# design.net
KiCad netlist of a schematic drawn in Altium Designer
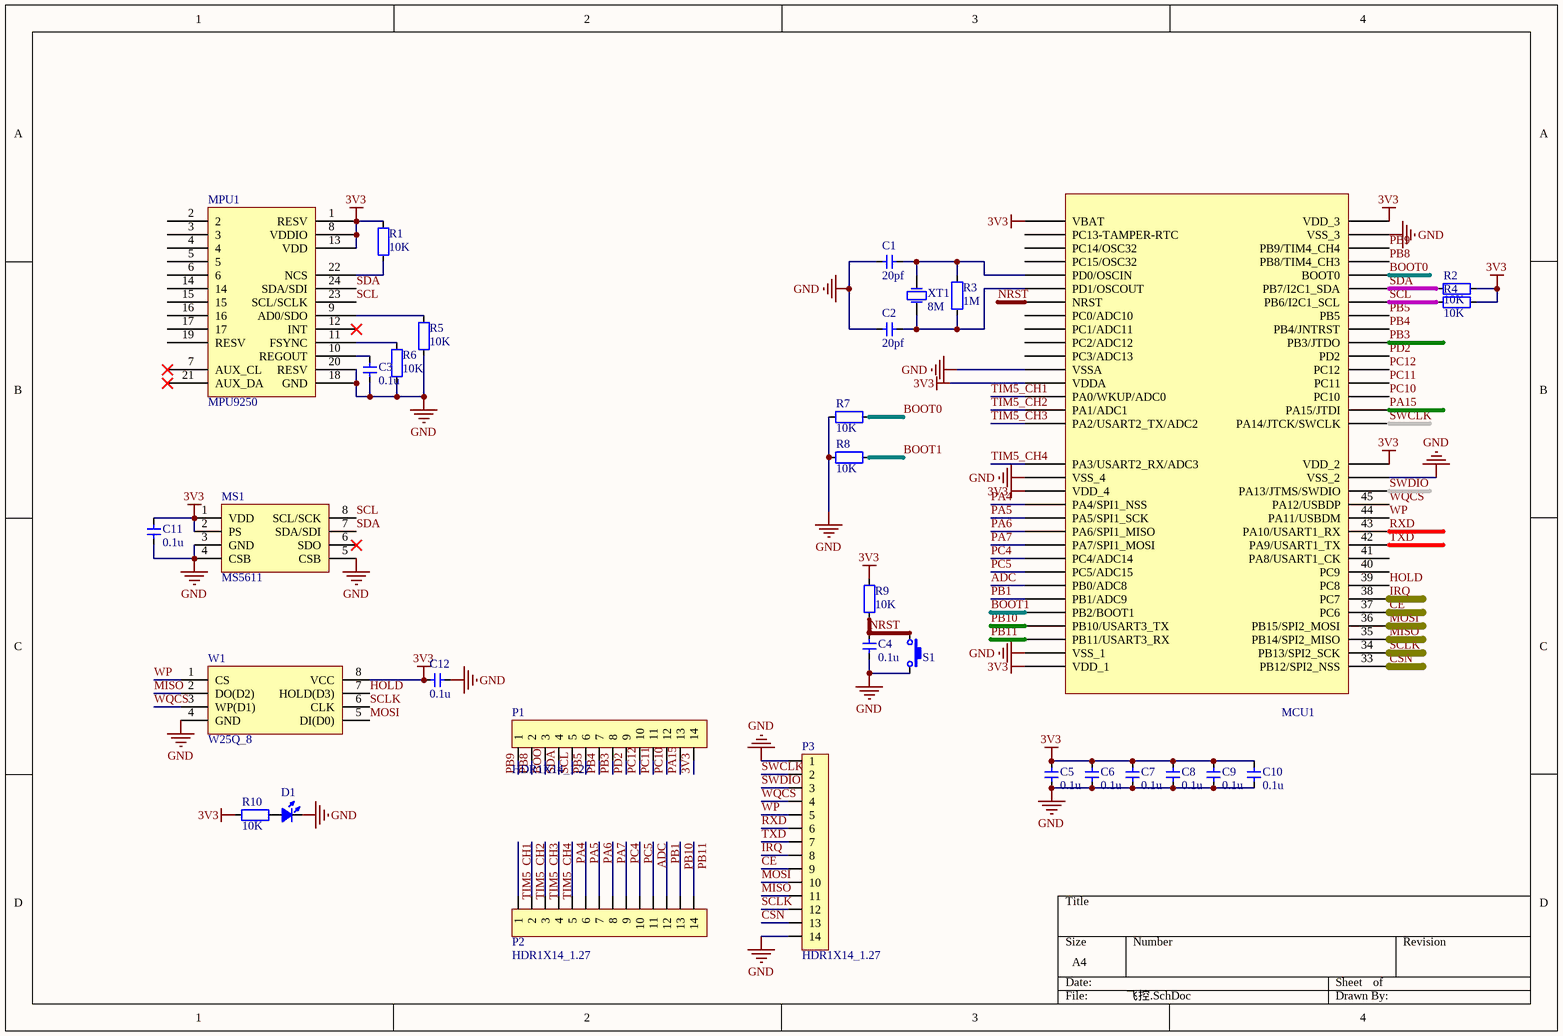
[diagram p0: 飞控.SchDoc]

(export (version "E")
  (design (tool "Eeschema 10.0.6"))
  (components
    (comp (ref "C1")
      (value "20pf")
      (footprint "PCB_PassiveCap:CAP_0603")
      (description "Capacitor")
      (fields (field (name "Comment") "Cap_0603"))
      (libsource (lib "SCH_Passive") (part "Cap_0603"))
    )
    (comp (ref "C2")
      (value "20pf")
      (footprint "PCB_PassiveCap:CAP_0603")
      (description "Capacitor")
      (fields (field (name "Comment") "Cap_0603"))
      (libsource (lib "SCH_Passive") (part "Cap_0603"))
    )
    (comp (ref "C3")
      (value "0.1u")
      (footprint "PCB_PassiveCap:CAP_0603")
      (description "Capacitor")
      (fields (field (name "Comment") "Cap_0603"))
      (libsource (lib "SCH_Passive") (part "Cap_0603"))
    )
    (comp (ref "C4")
      (value "0.1u")
      (footprint "PCB_PassiveCap:CAP_0603")
      (description "Capacitor")
      (fields (field (name "Comment") "Cap_0603"))
      (libsource (lib "SCH_Passive") (part "Cap_0603"))
    )
    (comp (ref "C5")
      (value "0.1u")
      (footprint "PCB_PassiveCap:CAP_0603")
      (description "Capacitor")
      (fields (field (name "Comment") "Cap_0603"))
      (libsource (lib "SCH_Passive") (part "Cap_0603"))
    )
    (comp (ref "C6")
      (value "0.1u")
      (footprint "PCB_PassiveCap:CAP_0603")
      (description "Capacitor")
      (fields (field (name "Comment") "Cap_0603"))
      (libsource (lib "SCH_Passive") (part "Cap_0603"))
    )
    (comp (ref "C7")
      (value "0.1u")
      (footprint "PCB_PassiveCap:CAP_0603")
      (description "Capacitor")
      (fields (field (name "Comment") "Cap_0603"))
      (libsource (lib "SCH_Passive") (part "Cap_0603"))
    )
    (comp (ref "C8")
      (value "0.1u")
      (footprint "PCB_PassiveCap:CAP_0603")
      (description "Capacitor")
      (fields (field (name "Comment") "Cap_0603"))
      (libsource (lib "SCH_Passive") (part "Cap_0603"))
    )
    (comp (ref "C9")
      (value "0.1u")
      (footprint "PCB_PassiveCap:CAP_0603")
      (description "Capacitor")
      (fields (field (name "Comment") "Cap_0603"))
      (libsource (lib "SCH_Passive") (part "Cap_0603"))
    )
    (comp (ref "C10")
      (value "0.1u")
      (footprint "PCB_PassiveCap:CAP_0603")
      (description "Capacitor")
      (fields (field (name "Comment") "Cap_0603"))
      (libsource (lib "SCH_Passive") (part "Cap_0603"))
    )
    (comp (ref "C11")
      (value "0.1u")
      (footprint "PCB_PassiveCap:CAP_0603")
      (description "Capacitor")
      (fields (field (name "Comment") "Cap_0603"))
      (libsource (lib "SCH_Passive") (part "Cap_0603"))
    )
    (comp (ref "C12")
      (value "0.1u")
      (footprint "PCB_PassiveCap:CAP_0603")
      (description "Capacitor")
      (fields (field (name "Comment") "Cap_0603"))
      (libsource (lib "SCH_Passive") (part "Cap_0603"))
    )
    (comp (ref "D1")
      (value "LED_0805")
      (footprint "PCB_ActiveLED:LED_0805_RED")
      (description "LED")
      (libsource (lib "SCH_Active") (part "LED_0805"))
    )
    (comp (ref "MCU1")
      (value "STM32F103RC")
      (footprint "LQFP_P0.5_64")
      (description "MCU")
      (libsource (lib "SCH_IntegratedCircuit") (part "STM32F103RC"))
    )
    (comp (ref "MPU1")
      (value "MPU9250")
      (footprint "QFN_P0.4_24")
      (libsource (lib "K60-mainboard-v3.1") (part "MPU9250"))
    )
    (comp (ref "MS1")
      (value "MS5611")
      (footprint "PCB_IntegratedCircuit:OTHER_MS5611_8")
      (description "Sensor")
      (libsource (lib "SCH_IntegratedCircuit") (part "MS5611"))
    )
    (comp (ref "P1")
      (value "HDR1X14_1.27")
      (footprint "HDR1X14_1.27")
      (libsource (lib "") (part "HDR1X14_1.27_2"))
    )
    (comp (ref "P2")
      (value "HDR1X14_1.27")
      (footprint "HDR1X14_1.27")
      (libsource (lib "") (part "HDR1X14_1.27_1"))
    )
    (comp (ref "P3")
      (value "HDR1X14_1.27")
      (footprint "HDR1X14_1.27")
      (libsource (lib "SCH_ConnectorHDR") (part "HDR1X14_1.27"))
    )
    (comp (ref "R1")
      (value "10K")
      (footprint "PCB_PassiveRes:RES_0603")
      (description "Resistor")
      (fields (field (name "Comment") "Res_0603"))
      (libsource (lib "SCH_Passive") (part "Res_0603"))
    )
    (comp (ref "R2")
      (value "10K")
      (footprint "PCB_PassiveRes:RES_0603")
      (description "Resistor")
      (fields (field (name "Comment") "Res_0603"))
      (libsource (lib "") (part "Res_0603_1"))
    )
    (comp (ref "R3")
      (value "1M")
      (footprint "PCB_PassiveRes:RES_0603")
      (description "Resistor")
      (fields (field (name "Comment") "Res_0603"))
      (libsource (lib "") (part "Res_0603_2"))
    )
    (comp (ref "R4")
      (value "10K")
      (footprint "PCB_PassiveRes:RES_0603")
      (description "Resistor")
      (fields (field (name "Comment") "Res_0603"))
      (libsource (lib "") (part "Res_0603_1"))
    )
    (comp (ref "R5")
      (value "10K")
      (footprint "PCB_PassiveRes:RES_0603")
      (description "Resistor")
      (fields (field (name "Comment") "Res_0603"))
      (libsource (lib "SCH_Passive") (part "Res_0603"))
    )
    (comp (ref "R6")
      (value "10K")
      (footprint "PCB_PassiveRes:RES_0603")
      (description "Resistor")
      (fields (field (name "Comment") "Res_0603"))
      (libsource (lib "SCH_Passive") (part "Res_0603"))
    )
    (comp (ref "R7")
      (value "10K")
      (footprint "PCB_PassiveRes:RES_0603")
      (description "Resistor")
      (fields (field (name "Comment") "Res_0603"))
      (libsource (lib "") (part "Res_0603_3"))
    )
    (comp (ref "R8")
      (value "10K")
      (footprint "PCB_PassiveRes:RES_0603")
      (description "Resistor")
      (fields (field (name "Comment") "Res_0603"))
      (libsource (lib "") (part "Res_0603_3"))
    )
    (comp (ref "R9")
      (value "10K")
      (footprint "PCB_PassiveRes:RES_0603")
      (description "Resistor")
      (fields (field (name "Comment") "Res_0603"))
      (libsource (lib "SCH_Passive") (part "Res_0603"))
    )
    (comp (ref "R10")
      (value "10K")
      (footprint "PCB_PassiveRes:RES_0603")
      (description "Resistor")
      (fields (field (name "Comment") "Res_0603"))
      (libsource (lib "") (part "Res_0603_1"))
    )
    (comp (ref "S1")
      (value "ButtonTACT_3x4x2_180")
      (footprint "PCB_Switch:ButtonTACT_3x4x2_180H")
      (description "Button")
      (libsource (lib "SCH_Switch") (part "ButtonTACT_3x4x2_180"))
    )
    (comp (ref "W1")
      (value "W25Q_8")
      (footprint "PCB_IntegratedCircuit:SOIC_E200_8")
      (description "FLASH")
      (libsource (lib "SCH_IntegratedCircuit") (part "W25Q_8"))
    )
    (comp (ref "XT1")
      (value "8M")
      (footprint "PCB_Oscillator:XT_5032_2")
      (description "Crystal Oscillator")
      (fields (field (name "Comment") "XTAL_5032_2P"))
      (libsource (lib "SCH_Oscillator") (part "XTAL_5032_2P"))
    )
  )
  (nets
    (net (code "1") (name "/ADC") (class "Default")
      (node (ref "MCU1") (pin "26") (pinfunction "PB0/ADC8_26") (pintype "passive"))
      (node (ref "P2") (pin "11") (pinfunction "11_11") (pintype "passive"))
    )
    (net (code "2") (name "/BOOT0") (class "Default")
      (node (ref "MCU1") (pin "60") (pinfunction "BOOT0_60") (pintype "passive"))
      (node (ref "P1") (pin "3") (pinfunction "3_3") (pintype "passive"))
      (node (ref "R7") (pin "1") (pinfunction "1_1") (pintype "passive"))
    )
    (net (code "3") (name "/BOOT1") (class "Default")
      (node (ref "MCU1") (pin "28") (pinfunction "PB2/BOOT1_28") (pintype "passive"))
      (node (ref "R8") (pin "1") (pinfunction "1_1") (pintype "passive"))
    )
    (net (code "4") (name "/CE") (class "Default")
      (node (ref "MCU1") (pin "37") (pinfunction "PC6_37") (pintype "passive"))
      (node (ref "P3") (pin "9") (pinfunction "9_9") (pintype "passive"))
    )
    (net (code "5") (name "/CSN") (class "Default")
      (node (ref "MCU1") (pin "33") (pinfunction "PB12/SPI2_NSS_33") (pintype "passive"))
      (node (ref "P3") (pin "13") (pinfunction "13_13") (pintype "passive"))
    )
    (net (code "6") (name "/HOLD") (class "Default")
      (node (ref "MCU1") (pin "39") (pinfunction "PC8_39") (pintype "passive"))
      (node (ref "W1") (pin "7") (pinfunction "HOLD(D3)_7") (pintype "passive"))
    )
    (net (code "7") (name "/IRQ") (class "Default")
      (node (ref "MCU1") (pin "38") (pinfunction "PC7_38") (pintype "passive"))
      (node (ref "P3") (pin "8") (pinfunction "8_8") (pintype "passive"))
    )
    (net (code "8") (name "/MISO") (class "Default")
      (node (ref "MCU1") (pin "35") (pinfunction "PB14/SPI2_MISO_35") (pintype "passive"))
      (node (ref "P3") (pin "11") (pinfunction "11_11") (pintype "passive"))
      (node (ref "W1") (pin "2") (pinfunction "DO(D2)_2") (pintype "passive"))
    )
    (net (code "9") (name "/MOSI") (class "Default")
      (node (ref "MCU1") (pin "36") (pinfunction "PB15/SPI2_MOSI_36") (pintype "passive"))
      (node (ref "P3") (pin "10") (pinfunction "10_10") (pintype "passive"))
      (node (ref "W1") (pin "5") (pinfunction "DI(D0)_5") (pintype "passive"))
    )
    (net (code "10") (name "/NRST") (class "Default")
      (node (ref "C4") (pin "2") (pinfunction "2_2") (pintype "passive"))
      (node (ref "MCU1") (pin "7") (pinfunction "NRST_7") (pintype "passive"))
      (node (ref "R9") (pin "2") (pinfunction "2_2") (pintype "passive"))
      (node (ref "S1") (pin "1") (pinfunction "1_1") (pintype "passive"))
    )
    (net (code "11") (name "/PA4") (class "Default")
      (node (ref "MCU1") (pin "20") (pinfunction "PA4/SPI1_NSS_20") (pintype "passive"))
      (node (ref "P2") (pin "5") (pinfunction "5_5") (pintype "passive"))
    )
    (net (code "12") (name "/PA5") (class "Default")
      (node (ref "MCU1") (pin "21") (pinfunction "PA5/SPI1_SCK_21") (pintype "passive"))
      (node (ref "P2") (pin "6") (pinfunction "6_6") (pintype "passive"))
    )
    (net (code "13") (name "/PA6") (class "Default")
      (node (ref "MCU1") (pin "22") (pinfunction "PA6/SPI1_MISO_22") (pintype "passive"))
      (node (ref "P2") (pin "7") (pinfunction "7_7") (pintype "passive"))
    )
    (net (code "14") (name "/PA7") (class "Default")
      (node (ref "MCU1") (pin "23") (pinfunction "PA7/SPI1_MOSI_23") (pintype "passive"))
      (node (ref "P2") (pin "8") (pinfunction "8_8") (pintype "passive"))
    )
    (net (code "15") (name "/PA15") (class "Default")
      (node (ref "MCU1") (pin "50") (pinfunction "PA15/JTDI_50") (pintype "passive"))
      (node (ref "P1") (pin "13") (pinfunction "13_13") (pintype "passive"))
    )
    (net (code "16") (name "/PB1") (class "Default")
      (node (ref "MCU1") (pin "27") (pinfunction "PB1/ADC9_27") (pintype "passive"))
      (node (ref "P2") (pin "12") (pinfunction "12_12") (pintype "passive"))
    )
    (net (code "17") (name "/PB3") (class "Default")
      (node (ref "MCU1") (pin "55") (pinfunction "PB3/JTDO_55") (pintype "passive"))
      (node (ref "P1") (pin "8") (pinfunction "8_8") (pintype "passive"))
    )
    (net (code "18") (name "/PB4") (class "Default")
      (node (ref "MCU1") (pin "56") (pinfunction "PB4/JNTRST_56") (pintype "passive"))
      (node (ref "P1") (pin "7") (pinfunction "7_7") (pintype "passive"))
    )
    (net (code "19") (name "/PB5") (class "Default")
      (node (ref "MCU1") (pin "57") (pinfunction "PB5_57") (pintype "passive"))
      (node (ref "P1") (pin "6") (pinfunction "6_6") (pintype "passive"))
    )
    (net (code "20") (name "/PB8") (class "Default")
      (node (ref "MCU1") (pin "61") (pinfunction "PB8/TIM4_CH3_61") (pintype "passive"))
      (node (ref "P1") (pin "2") (pinfunction "2_2") (pintype "passive"))
    )
    (net (code "21") (name "/PB9") (class "Default")
      (node (ref "MCU1") (pin "62") (pinfunction "PB9/TIM4_CH4_62") (pintype "passive"))
      (node (ref "P1") (pin "1") (pinfunction "1_1") (pintype "passive"))
    )
    (net (code "22") (name "/PB10") (class "Default")
      (node (ref "MCU1") (pin "29") (pinfunction "PB10/USART3_TX_29") (pintype "passive"))
      (node (ref "P2") (pin "13") (pinfunction "13_13") (pintype "passive"))
    )
    (net (code "23") (name "/PB11") (class "Default")
      (node (ref "MCU1") (pin "30") (pinfunction "PB11/USART3_RX_30") (pintype "passive"))
      (node (ref "P2") (pin "14") (pinfunction "14_14") (pintype "passive"))
    )
    (net (code "24") (name "/PC4") (class "Default")
      (node (ref "MCU1") (pin "24") (pinfunction "PC4/ADC14_24") (pintype "passive"))
      (node (ref "P2") (pin "9") (pinfunction "9_9") (pintype "passive"))
    )
    (net (code "25") (name "/PC5") (class "Default")
      (node (ref "MCU1") (pin "25") (pinfunction "PC5/ADC15_25") (pintype "passive"))
      (node (ref "P2") (pin "10") (pinfunction "10_10") (pintype "passive"))
    )
    (net (code "26") (name "/PC10") (class "Default")
      (node (ref "MCU1") (pin "51") (pinfunction "PC10_51") (pintype "passive"))
      (node (ref "P1") (pin "12") (pinfunction "12_12") (pintype "passive"))
    )
    (net (code "27") (name "/PC11") (class "Default")
      (node (ref "MCU1") (pin "52") (pinfunction "PC11_52") (pintype "passive"))
      (node (ref "P1") (pin "11") (pinfunction "11_11") (pintype "passive"))
    )
    (net (code "28") (name "/PC12") (class "Default")
      (node (ref "MCU1") (pin "53") (pinfunction "PC12_53") (pintype "passive"))
      (node (ref "P1") (pin "10") (pinfunction "10_10") (pintype "passive"))
    )
    (net (code "29") (name "/PD2") (class "Default")
      (node (ref "MCU1") (pin "54") (pinfunction "PD2_54") (pintype "passive"))
      (node (ref "P1") (pin "9") (pinfunction "9_9") (pintype "passive"))
    )
    (net (code "30") (name "/RXD") (class "Default")
      (node (ref "MCU1") (pin "43") (pinfunction "PA10/USART1_RX_43") (pintype "passive"))
      (node (ref "P3") (pin "6") (pinfunction "6_6") (pintype "passive"))
    )
    (net (code "31") (name "/SCL") (class "Default")
      (node (ref "MCU1") (pin "58") (pinfunction "PB6/I2C1_SCL_58") (pintype "passive"))
      (node (ref "MPU1") (pin "23") (pinfunction "SCL/SCLK_23") (pintype "passive"))
      (node (ref "MS1") (pin "8") (pinfunction "SCL/SCK_8") (pintype "passive"))
      (node (ref "P1") (pin "5") (pinfunction "5_5") (pintype "passive"))
      (node (ref "R4") (pin "1") (pinfunction "1_1") (pintype "passive"))
    )
    (net (code "32") (name "/SCLK") (class "Default")
      (node (ref "MCU1") (pin "34") (pinfunction "PB13/SPI2_SCK_34") (pintype "passive"))
      (node (ref "P3") (pin "12") (pinfunction "12_12") (pintype "passive"))
      (node (ref "W1") (pin "6") (pinfunction "CLK_6") (pintype "passive"))
    )
    (net (code "33") (name "/SDA") (class "Default")
      (node (ref "MCU1") (pin "59") (pinfunction "PB7/I2C1_SDA_59") (pintype "passive"))
      (node (ref "MPU1") (pin "24") (pinfunction "SDA/SDI_24") (pintype "passive"))
      (node (ref "MS1") (pin "7") (pinfunction "SDA/SDI_7") (pintype "passive"))
      (node (ref "P1") (pin "4") (pinfunction "4_4") (pintype "passive"))
      (node (ref "R2") (pin "1") (pinfunction "1_1") (pintype "passive"))
    )
    (net (code "34") (name "/SWCLK") (class "Default")
      (node (ref "MCU1") (pin "49") (pinfunction "PA14/JTCK/SWCLK_49") (pintype "passive"))
      (node (ref "P3") (pin "2") (pinfunction "2_2") (pintype "passive"))
    )
    (net (code "35") (name "/SWDIO") (class "Default")
      (node (ref "MCU1") (pin "46") (pinfunction "PA13/JTMS/SWDIO_46") (pintype "passive"))
      (node (ref "P3") (pin "3") (pinfunction "3_3") (pintype "passive"))
    )
    (net (code "36") (name "/TIM5_CH1") (class "Default")
      (node (ref "MCU1") (pin "14") (pinfunction "PA0/WKUP/ADC0_14") (pintype "passive"))
      (node (ref "P2") (pin "1") (pinfunction "1_1") (pintype "passive"))
    )
    (net (code "37") (name "/TIM5_CH2") (class "Default")
      (node (ref "MCU1") (pin "15") (pinfunction "PA1/ADC1_15") (pintype "passive"))
      (node (ref "P2") (pin "2") (pinfunction "2_2") (pintype "passive"))
    )
    (net (code "38") (name "/TIM5_CH3") (class "Default")
      (node (ref "MCU1") (pin "16") (pinfunction "PA2/USART2_TX/ADC2_16") (pintype "passive"))
      (node (ref "P2") (pin "3") (pinfunction "3_3") (pintype "passive"))
    )
    (net (code "39") (name "/TIM5_CH4") (class "Default")
      (node (ref "MCU1") (pin "17") (pinfunction "PA3/USART2_RX/ADC3_17") (pintype "passive"))
      (node (ref "P2") (pin "4") (pinfunction "4_4") (pintype "passive"))
    )
    (net (code "40") (name "/TXD") (class "Default")
      (node (ref "MCU1") (pin "42") (pinfunction "PA9/USART1_TX_42") (pintype "passive"))
      (node (ref "P3") (pin "7") (pinfunction "7_7") (pintype "passive"))
    )
    (net (code "41") (name "/WP") (class "Default")
      (node (ref "MCU1") (pin "44") (pinfunction "PA11/USBDM_44") (pintype "passive"))
      (node (ref "P3") (pin "5") (pinfunction "5_5") (pintype "passive"))
      (node (ref "W1") (pin "1") (pinfunction "CS_1") (pintype "passive"))
    )
    (net (code "42") (name "/WQCS") (class "Default")
      (node (ref "MCU1") (pin "45") (pinfunction "PA12/USBDP_45") (pintype "passive"))
      (node (ref "P3") (pin "4") (pinfunction "4_4") (pintype "passive"))
      (node (ref "W1") (pin "3") (pinfunction "WP(D1)_3") (pintype "passive"))
    )
    (net (code "43") (name "3V3") (class "Default")
      (node (ref "C10") (pin "2") (pinfunction "2_2") (pintype "passive"))
      (node (ref "C11") (pin "2") (pinfunction "2_2") (pintype "passive"))
      (node (ref "C12") (pin "1") (pinfunction "1_1") (pintype "passive"))
      (node (ref "C5") (pin "2") (pinfunction "2_2") (pintype "passive"))
      (node (ref "C6") (pin "2") (pinfunction "2_2") (pintype "passive"))
      (node (ref "C7") (pin "2") (pinfunction "2_2") (pintype "passive"))
      (node (ref "C8") (pin "2") (pinfunction "2_2") (pintype "passive"))
      (node (ref "C9") (pin "2") (pinfunction "2_2") (pintype "passive"))
      (node (ref "MCU1") (pin "1") (pinfunction "VBAT_1") (pintype "passive"))
      (node (ref "MCU1") (pin "13") (pinfunction "VDDA_13") (pintype "passive"))
      (node (ref "MCU1") (pin "19") (pinfunction "VDD_4_19") (pintype "passive"))
      (node (ref "MCU1") (pin "32") (pinfunction "VDD_1_32") (pintype "passive"))
      (node (ref "MCU1") (pin "48") (pinfunction "VDD_2_48") (pintype "passive"))
      (node (ref "MCU1") (pin "64") (pinfunction "VDD_3_64") (pintype "passive"))
      (node (ref "MPU1") (pin "1") (pinfunction "RESV_1") (pintype "passive"))
      (node (ref "MPU1") (pin "13") (pinfunction "VDD_13") (pintype "passive"))
      (node (ref "MPU1") (pin "8") (pinfunction "VDDIO_8") (pintype "passive"))
      (node (ref "MS1") (pin "1") (pinfunction "VDD_1") (pintype "passive"))
      (node (ref "MS1") (pin "2") (pinfunction "PS_2") (pintype "passive"))
      (node (ref "P1") (pin "14") (pinfunction "14_14") (pintype "passive"))
      (node (ref "R1") (pin "1") (pinfunction "1_1") (pintype "passive"))
      (node (ref "R10") (pin "1") (pinfunction "1_1") (pintype "passive"))
      (node (ref "R2") (pin "2") (pinfunction "2_2") (pintype "passive"))
      (node (ref "R4") (pin "2") (pinfunction "2_2") (pintype "passive"))
      (node (ref "R9") (pin "1") (pinfunction "1_1") (pintype "passive"))
      (node (ref "W1") (pin "8") (pinfunction "VCC_8") (pintype "passive"))
    )
    (net (code "44") (name "GND") (class "Default")
      (node (ref "C1") (pin "1") (pinfunction "1_1") (pintype "passive"))
      (node (ref "C10") (pin "1") (pinfunction "1_1") (pintype "passive"))
      (node (ref "C11") (pin "1") (pinfunction "1_1") (pintype "passive"))
      (node (ref "C12") (pin "2") (pinfunction "2_2") (pintype "passive"))
      (node (ref "C2") (pin "1") (pinfunction "1_1") (pintype "passive"))
      (node (ref "C3") (pin "2") (pinfunction "2_2") (pintype "passive"))
      (node (ref "C4") (pin "1") (pinfunction "1_1") (pintype "passive"))
      (node (ref "C5") (pin "1") (pinfunction "1_1") (pintype "passive"))
      (node (ref "C6") (pin "1") (pinfunction "1_1") (pintype "passive"))
      (node (ref "C7") (pin "1") (pinfunction "1_1") (pintype "passive"))
      (node (ref "C8") (pin "1") (pinfunction "1_1") (pintype "passive"))
      (node (ref "C9") (pin "1") (pinfunction "1_1") (pintype "passive"))
      (node (ref "D1") (pin "2") (pinfunction "K_2") (pintype "passive"))
      (node (ref "MCU1") (pin "12") (pinfunction "VSSA_12") (pintype "passive"))
      (node (ref "MCU1") (pin "18") (pinfunction "VSS_4_18") (pintype "passive"))
      (node (ref "MCU1") (pin "31") (pinfunction "VSS_1_31") (pintype "passive"))
      (node (ref "MCU1") (pin "47") (pinfunction "VSS_2_47") (pintype "passive"))
      (node (ref "MCU1") (pin "63") (pinfunction "VSS_3_63") (pintype "passive"))
      (node (ref "MPU1") (pin "18") (pinfunction "GND_18") (pintype "passive"))
      (node (ref "MPU1") (pin "20") (pinfunction "RESV_20") (pintype "passive"))
      (node (ref "MS1") (pin "3") (pinfunction "GND_3") (pintype "passive"))
      (node (ref "MS1") (pin "4") (pinfunction "CSB_4") (pintype "passive"))
      (node (ref "MS1") (pin "5") (pinfunction "CSB_5") (pintype "passive"))
      (node (ref "P3") (pin "1") (pinfunction "1_1") (pintype "passive"))
      (node (ref "P3") (pin "14") (pinfunction "14_14") (pintype "passive"))
      (node (ref "R5") (pin "2") (pinfunction "2_2") (pintype "passive"))
      (node (ref "R6") (pin "2") (pinfunction "2_2") (pintype "passive"))
      (node (ref "R7") (pin "2") (pinfunction "2_2") (pintype "passive"))
      (node (ref "R8") (pin "2") (pinfunction "2_2") (pintype "passive"))
      (node (ref "S1") (pin "2") (pinfunction "2_2") (pintype "passive"))
      (node (ref "W1") (pin "4") (pinfunction "GND_4") (pintype "passive"))
    )
    (net (code "45") (name "Net-(D1-A)") (class "Default")
      (node (ref "D1") (pin "1") (pinfunction "A_1") (pintype "passive"))
      (node (ref "R10") (pin "2") (pinfunction "2_2") (pintype "passive"))
    )
    (net (code "46") (name "Net-(MCU1-PD0{slash}OSCIN)") (class "Default")
      (node (ref "C1") (pin "2") (pinfunction "2_2") (pintype "passive"))
      (node (ref "MCU1") (pin "5") (pinfunction "PD0/OSCIN_5") (pintype "passive"))
      (node (ref "R3") (pin "2") (pinfunction "2_2") (pintype "passive"))
      (node (ref "XT1") (pin "2") (pinfunction "OSC2_2") (pintype "passive"))
    )
    (net (code "47") (name "Net-(MCU1-PD1{slash}OSCOUT)") (class "Default")
      (node (ref "C2") (pin "2") (pinfunction "2_2") (pintype "passive"))
      (node (ref "MCU1") (pin "6") (pinfunction "PD1/OSCOUT_6") (pintype "passive"))
      (node (ref "R3") (pin "1") (pinfunction "1_1") (pintype "passive"))
      (node (ref "XT1") (pin "1") (pinfunction "OSC1_1") (pintype "passive"))
    )
    (net (code "48") (name "Net-(MPU1-AD0{slash}SDO)") (class "Default")
      (node (ref "MPU1") (pin "9") (pinfunction "AD0/SDO_9") (pintype "passive"))
      (node (ref "R5") (pin "1") (pinfunction "1_1") (pintype "passive"))
    )
    (net (code "49") (name "Net-(MPU1-FSYNC)") (class "Default")
      (node (ref "MPU1") (pin "11") (pinfunction "FSYNC_11") (pintype "passive"))
      (node (ref "R6") (pin "1") (pinfunction "1_1") (pintype "passive"))
    )
    (net (code "50") (name "Net-(MPU1-NCS)") (class "Default")
      (node (ref "MPU1") (pin "22") (pinfunction "NCS_22") (pintype "passive"))
      (node (ref "R1") (pin "2") (pinfunction "2_2") (pintype "passive"))
    )
    (net (code "51") (name "Net-(MPU1-REGOUT)") (class "Default")
      (node (ref "C3") (pin "1") (pinfunction "1_1") (pintype "passive"))
      (node (ref "MPU1") (pin "10") (pinfunction "REGOUT_10") (pintype "passive"))
    )
    (net (code "52") (name "unconnected-(MCU1-PA8{slash}USART1_CK-Pad41)") (class "Default")
      (node (ref "MCU1") (pin "41") (pinfunction "PA8/USART1_CK_41") (pintype "passive"))
    )
    (net (code "53") (name "unconnected-(MCU1-PC0{slash}ADC10-Pad8)") (class "Default")
      (node (ref "MCU1") (pin "8") (pinfunction "PC0/ADC10_8") (pintype "passive"))
    )
    (net (code "54") (name "unconnected-(MCU1-PC1{slash}ADC11-Pad9)") (class "Default")
      (node (ref "MCU1") (pin "9") (pinfunction "PC1/ADC11_9") (pintype "passive"))
    )
    (net (code "55") (name "unconnected-(MCU1-PC2{slash}ADC12-Pad10)") (class "Default")
      (node (ref "MCU1") (pin "10") (pinfunction "PC2/ADC12_10") (pintype "passive"))
    )
    (net (code "56") (name "unconnected-(MCU1-PC3{slash}ADC13-Pad11)") (class "Default")
      (node (ref "MCU1") (pin "11") (pinfunction "PC3/ADC13_11") (pintype "passive"))
    )
    (net (code "57") (name "unconnected-(MCU1-PC9-Pad40)") (class "Default")
      (node (ref "MCU1") (pin "40") (pinfunction "PC9_40") (pintype "passive"))
    )
    (net (code "58") (name "unconnected-(MCU1-PC13-TAMPER-RTC-Pad2)") (class "Default")
      (node (ref "MCU1") (pin "2") (pinfunction "PC13-TAMPER-RTC_2") (pintype "passive"))
    )
    (net (code "59") (name "unconnected-(MCU1-PC14{slash}OSC32-Pad3)") (class "Default")
      (node (ref "MCU1") (pin "3") (pinfunction "PC14/OSC32_3") (pintype "passive"))
    )
    (net (code "60") (name "unconnected-(MCU1-PC15{slash}OSC32-Pad4)") (class "Default")
      (node (ref "MCU1") (pin "4") (pinfunction "PC15/OSC32_4") (pintype "passive"))
    )
    (net (code "61") (name "unconnected-(MPU1-AUX_CL-Pad7)") (class "Default")
      (node (ref "MPU1") (pin "7") (pinfunction "AUX_CL_7") (pintype "passive+no_connect"))
    )
    (net (code "62") (name "unconnected-(MPU1-AUX_DA-Pad21)") (class "Default")
      (node (ref "MPU1") (pin "21") (pinfunction "AUX_DA_21") (pintype "passive+no_connect"))
    )
    (net (code "63") (name "unconnected-(MPU1-INT-Pad12)") (class "Default")
      (node (ref "MPU1") (pin "12") (pinfunction "INT_12") (pintype "passive+no_connect"))
    )
    (net (code "64") (name "unconnected-(MPU1-Pad2)") (class "Default")
      (node (ref "MPU1") (pin "2") (pinfunction "2_2") (pintype "passive"))
    )
    (net (code "65") (name "unconnected-(MPU1-Pad3)") (class "Default")
      (node (ref "MPU1") (pin "3") (pinfunction "3_3") (pintype "passive"))
    )
    (net (code "66") (name "unconnected-(MPU1-Pad4)") (class "Default")
      (node (ref "MPU1") (pin "4") (pinfunction "4_4") (pintype "passive"))
    )
    (net (code "67") (name "unconnected-(MPU1-Pad5)") (class "Default")
      (node (ref "MPU1") (pin "5") (pinfunction "5_5") (pintype "passive"))
    )
    (net (code "68") (name "unconnected-(MPU1-Pad6)") (class "Default")
      (node (ref "MPU1") (pin "6") (pinfunction "6_6") (pintype "passive"))
    )
    (net (code "69") (name "unconnected-(MPU1-Pad14)") (class "Default")
      (node (ref "MPU1") (pin "14") (pinfunction "14_14") (pintype "passive"))
    )
    (net (code "70") (name "unconnected-(MPU1-Pad15)") (class "Default")
      (node (ref "MPU1") (pin "15") (pinfunction "15_15") (pintype "passive"))
    )
    (net (code "71") (name "unconnected-(MPU1-Pad16)") (class "Default")
      (node (ref "MPU1") (pin "16") (pinfunction "16_16") (pintype "passive"))
    )
    (net (code "72") (name "unconnected-(MPU1-Pad17)") (class "Default")
      (node (ref "MPU1") (pin "17") (pinfunction "17_17") (pintype "passive"))
    )
    (net (code "73") (name "unconnected-(MPU1-RESV-Pad19)") (class "Default")
      (node (ref "MPU1") (pin "19") (pinfunction "RESV_19") (pintype "passive"))
    )
    (net (code "74") (name "unconnected-(MS1-SDO-Pad6)") (class "Default")
      (node (ref "MS1") (pin "6") (pinfunction "SDO_6") (pintype "passive+no_connect"))
    )
  )
)
